# D1MSHO.net
KiCad netlist of a schematic drawn in EAGLE
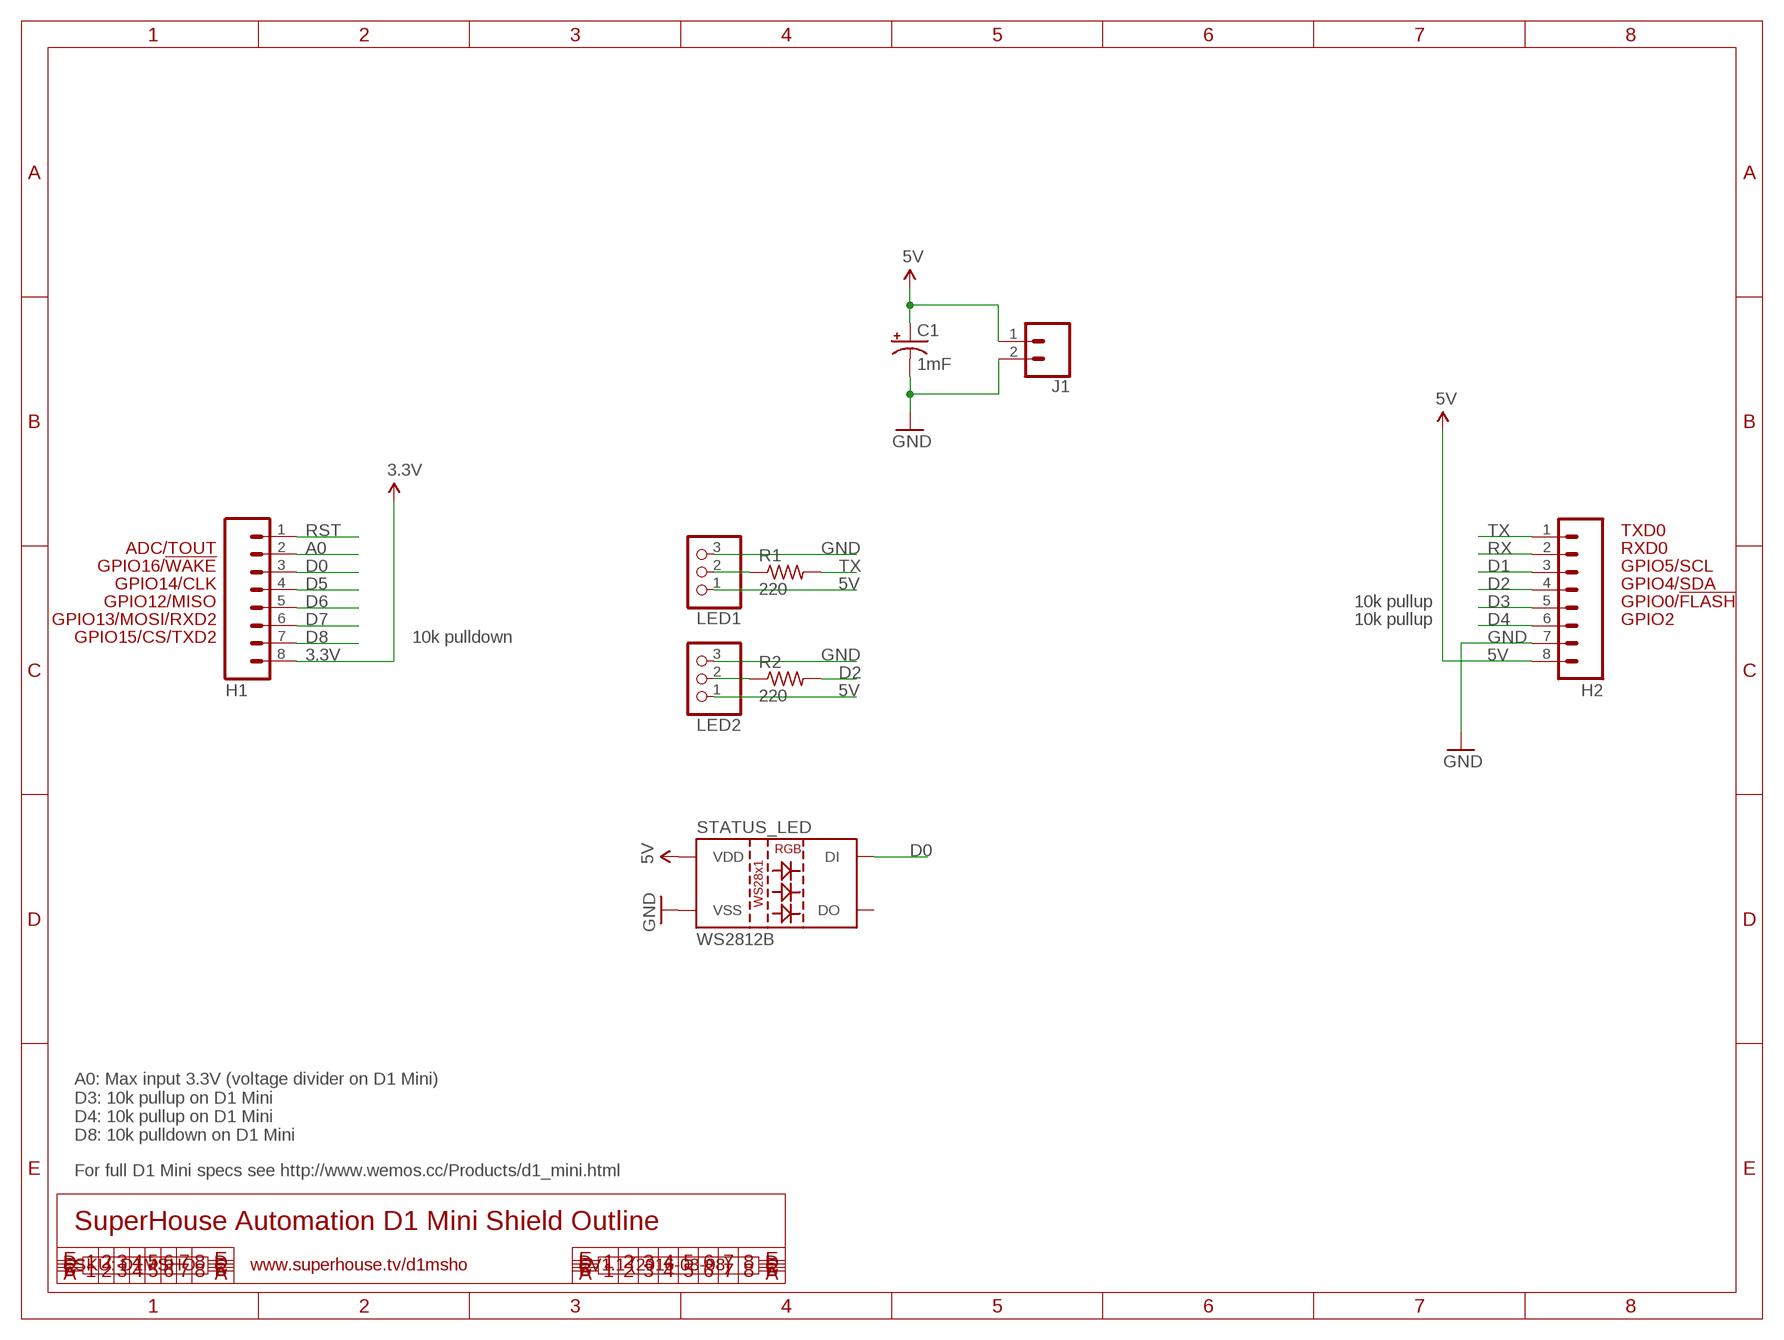
[diagram p0: schematic, sheet 1]

(export (version "E")
  (design (tool "Eeschema 10.0.6"))
  (components
    (comp (ref "C1")
      (value "1mF")
      (footprint "eagle-import:CPOL-RADIAL-5MM-10MM")
      (fields (field (name "SPICEPREFIX") "C"))
      (libsource (lib "eagle-import") (part "1000UF-RADIAL-5MM-25V-20%"))
    )
    (comp (ref "H1")
      (value "M08")
      (footprint "eagle-import:1X08")
      (libsource (lib "eagle-import") (part "M08"))
    )
    (comp (ref "H2")
      (value "M08")
      (footprint "eagle-import:1X08")
      (libsource (lib "eagle-import") (part "M08"))
    )
    (comp (ref "J1")
      (value "CONN_025MM")
      (footprint "eagle-import:SCREWTERMINAL-5MM-2")
      (libsource (lib "eagle-import") (part "CONN_025MM"))
    )
    (comp (ref "LED1")
      (value "PINHD-1X3")
      (footprint "eagle-import:1X03")
      (libsource (lib "eagle-import") (part "PINHD-1X3"))
    )
    (comp (ref "LED2")
      (value "PINHD-1X3")
      (footprint "eagle-import:1X03")
      (libsource (lib "eagle-import") (part "PINHD-1X3"))
    )
    (comp (ref "R1")
      (value "220")
      (footprint "eagle-import:0207_10")
      (libsource (lib "eagle-import") (part "R-US_0207/10"))
    )
    (comp (ref "R2")
      (value "220")
      (footprint "eagle-import:0207_10")
      (libsource (lib "eagle-import") (part "R-US_0207/10"))
    )
    (comp (ref "STATUS_LED")
      (value "WS2812B")
      (footprint "eagle-import:WS2812B")
      (libsource (lib "eagle-import") (part "WS2812B"))
    )
  )
  (nets
    (net (code "1") (name "/A0") (class "Default")
      (node (ref "H1") (pin "2") (pinfunction "2_2") (pintype "passive"))
    )
    (net (code "2") (name "/D0") (class "Default")
      (node (ref "H1") (pin "3") (pinfunction "3_3") (pintype "passive"))
      (node (ref "STATUS_LED") (pin "4") (pinfunction "DI_4") (pintype "bidirectional"))
    )
    (net (code "3") (name "/D1") (class "Default")
      (node (ref "H2") (pin "3") (pinfunction "3_3") (pintype "passive"))
    )
    (net (code "4") (name "/D2") (class "Default")
      (node (ref "H2") (pin "4") (pinfunction "4_4") (pintype "passive"))
      (node (ref "R2") (pin "2") (pinfunction "2_2") (pintype "passive"))
    )
    (net (code "5") (name "/D3") (class "Default")
      (node (ref "H2") (pin "5") (pinfunction "5_5") (pintype "passive"))
    )
    (net (code "6") (name "/D4") (class "Default")
      (node (ref "H2") (pin "6") (pinfunction "6_6") (pintype "passive"))
    )
    (net (code "7") (name "/D5") (class "Default")
      (node (ref "H1") (pin "4") (pinfunction "4_4") (pintype "passive"))
    )
    (net (code "8") (name "/D6") (class "Default")
      (node (ref "H1") (pin "5") (pinfunction "5_5") (pintype "passive"))
    )
    (net (code "9") (name "/D7") (class "Default")
      (node (ref "H1") (pin "6") (pinfunction "6_6") (pintype "passive"))
    )
    (net (code "10") (name "/D8") (class "Default")
      (node (ref "H1") (pin "7") (pinfunction "7_7") (pintype "passive"))
    )
    (net (code "11") (name "/RST") (class "Default")
      (node (ref "H1") (pin "1") (pinfunction "1_1") (pintype "passive"))
    )
    (net (code "12") (name "/RX") (class "Default")
      (node (ref "H2") (pin "2") (pinfunction "2_2") (pintype "passive"))
    )
    (net (code "13") (name "/TX") (class "Default")
      (node (ref "H2") (pin "1") (pinfunction "1_1") (pintype "passive"))
      (node (ref "R1") (pin "2") (pinfunction "2_2") (pintype "passive"))
    )
    (net (code "14") (name "3.3V") (class "Default")
      (node (ref "H1") (pin "8") (pinfunction "8_8") (pintype "passive"))
    )
    (net (code "15") (name "5V") (class "Default")
      (node (ref "C1") (pin "+") (pinfunction "+_+") (pintype "passive"))
      (node (ref "H2") (pin "8") (pinfunction "8_8") (pintype "passive"))
      (node (ref "J1") (pin "1") (pinfunction "1_1") (pintype "passive"))
      (node (ref "LED1") (pin "1") (pinfunction "1_1") (pintype "passive"))
      (node (ref "LED2") (pin "1") (pinfunction "1_1") (pintype "passive"))
      (node (ref "STATUS_LED") (pin "1") (pinfunction "VDD_1") (pintype "bidirectional"))
    )
    (net (code "16") (name "GND") (class "Default")
      (node (ref "C1") (pin "-") (pinfunction "-_-") (pintype "passive"))
      (node (ref "H2") (pin "7") (pinfunction "7_7") (pintype "passive"))
      (node (ref "J1") (pin "2") (pinfunction "2_2") (pintype "passive"))
      (node (ref "LED1") (pin "3") (pinfunction "3_3") (pintype "passive"))
      (node (ref "LED2") (pin "3") (pinfunction "3_3") (pintype "passive"))
      (node (ref "STATUS_LED") (pin "3") (pinfunction "VSS_3") (pintype "bidirectional"))
    )
    (net (code "17") (name "Net-(LED1-Pad2)") (class "Default")
      (node (ref "LED1") (pin "2") (pinfunction "2_2") (pintype "passive"))
      (node (ref "R1") (pin "1") (pinfunction "1_1") (pintype "passive"))
    )
    (net (code "18") (name "Net-(LED2-Pad2)") (class "Default")
      (node (ref "LED2") (pin "2") (pinfunction "2_2") (pintype "passive"))
      (node (ref "R2") (pin "1") (pinfunction "1_1") (pintype "passive"))
    )
    (net (code "19") (name "unconnected-(STATUS_LED-DO-Pad2)") (class "Default")
      (node (ref "STATUS_LED") (pin "2") (pinfunction "DO_2") (pintype "bidirectional"))
    )
  )
)
